# MCH_CON.net
KiCad netlist of a schematic drawn in Altium Designer
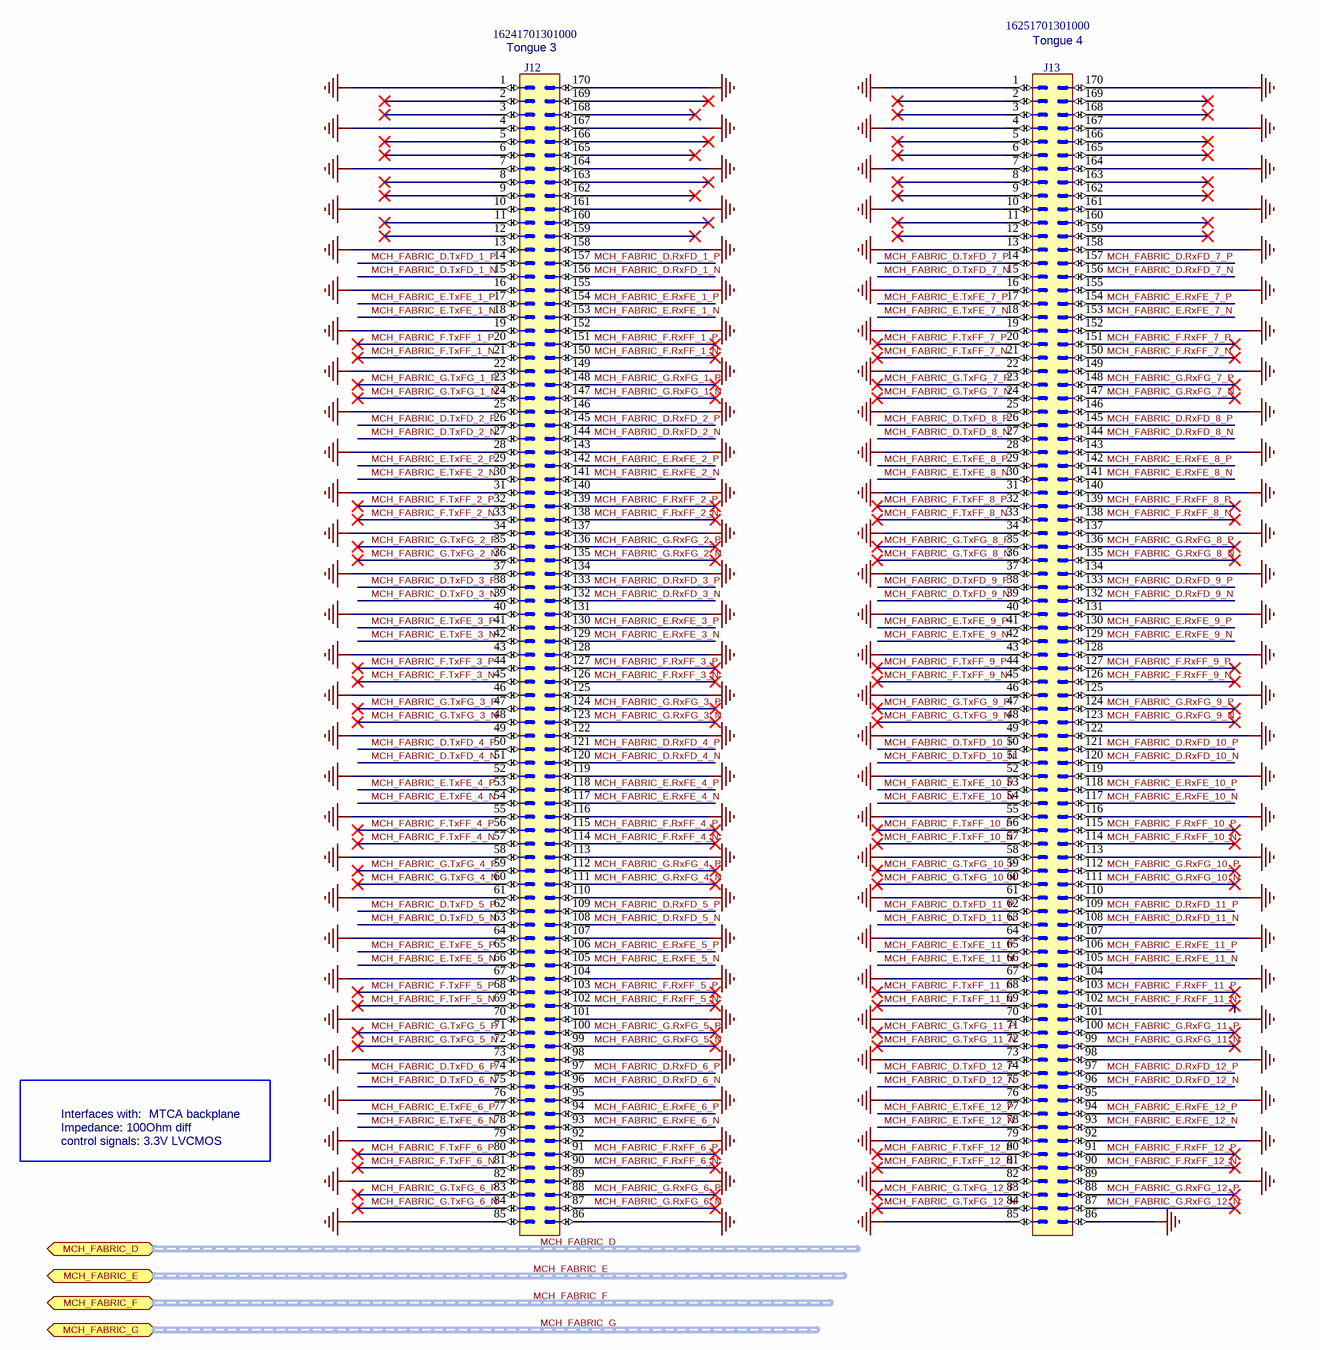
[diagram p0: MCH_CON.SchDoc]

(export (version "E")
  (design (tool "Eeschema 10.0.6"))
  (components
    (comp (ref "J12")
      (value "AdvancedMC")
      (footprint "ITB_16241701301000")
      (description "Connector 170 Male")
      (fields
        (field (name "MANUFACTURER PART NUMBER") "16241701301000")
        (field (name "MANUFACTURER") "ITB ADVANCED CONNECTORS")
        (field (name "PART NUMBER") "ITB_16241701301000")
        (field (name "AUTHOR") "CERN DEM MR")
      )
      (libsource (lib "Connectors") (part "Connector 170 Male"))
    )
    (comp (ref "J13")
      (value "AdvancedMC")
      (footprint "ITB_16251701301000")
      (description "Connector 170 Male")
      (fields
        (field (name "MANUFACTURER PART NUMBER") "16251701301000")
        (field (name "MANUFACTURER") "ITB ADVANCED CONNECTORS")
        (field (name "PART NUMBER") "ITB_16251701301000")
        (field (name "AUTHOR") "CERN DEM MR")
      )
      (libsource (lib "Connectors") (part "Connector 170 Male"))
    )
  )
  (nets
    (net (code "5") (name "/MCH_FABRIC_D.RxFD_1_N") (class "Default")
      (node (ref "J12") (pin "156") (pinfunction "156_156") (pintype "bidirectional"))
    )
    (net (code "6") (name "/MCH_FABRIC_D.RxFD_1_P") (class "Default")
      (node (ref "J12") (pin "157") (pinfunction "157_157") (pintype "bidirectional"))
    )
    (net (code "7") (name "/MCH_FABRIC_D.RxFD_2_N") (class "Default")
      (node (ref "J12") (pin "144") (pinfunction "144_144") (pintype "bidirectional"))
    )
    (net (code "8") (name "/MCH_FABRIC_D.RxFD_2_P") (class "Default")
      (node (ref "J12") (pin "145") (pinfunction "145_145") (pintype "bidirectional"))
    )
    (net (code "9") (name "/MCH_FABRIC_D.RxFD_3_N") (class "Default")
      (node (ref "J12") (pin "132") (pinfunction "132_132") (pintype "bidirectional"))
    )
    (net (code "10") (name "/MCH_FABRIC_D.RxFD_3_P") (class "Default")
      (node (ref "J12") (pin "133") (pinfunction "133_133") (pintype "bidirectional"))
    )
    (net (code "11") (name "/MCH_FABRIC_D.RxFD_4_N") (class "Default")
      (node (ref "J12") (pin "120") (pinfunction "120_120") (pintype "bidirectional"))
    )
    (net (code "12") (name "/MCH_FABRIC_D.RxFD_4_P") (class "Default")
      (node (ref "J12") (pin "121") (pinfunction "121_121") (pintype "bidirectional"))
    )
    (net (code "13") (name "/MCH_FABRIC_D.RxFD_5_N") (class "Default")
      (node (ref "J12") (pin "108") (pinfunction "108_108") (pintype "bidirectional"))
    )
    (net (code "14") (name "/MCH_FABRIC_D.RxFD_5_P") (class "Default")
      (node (ref "J12") (pin "109") (pinfunction "109_109") (pintype "bidirectional"))
    )
    (net (code "15") (name "/MCH_FABRIC_D.RxFD_6_N") (class "Default")
      (node (ref "J12") (pin "96") (pinfunction "96_96") (pintype "bidirectional"))
    )
    (net (code "16") (name "/MCH_FABRIC_D.RxFD_6_P") (class "Default")
      (node (ref "J12") (pin "97") (pinfunction "97_97") (pintype "bidirectional"))
    )
    (net (code "17") (name "/MCH_FABRIC_D.RxFD_7_N") (class "Default")
      (node (ref "J13") (pin "156") (pinfunction "156_156") (pintype "bidirectional"))
    )
    (net (code "18") (name "/MCH_FABRIC_D.RxFD_7_P") (class "Default")
      (node (ref "J13") (pin "157") (pinfunction "157_157") (pintype "bidirectional"))
    )
    (net (code "19") (name "/MCH_FABRIC_D.RxFD_8_N") (class "Default")
      (node (ref "J13") (pin "144") (pinfunction "144_144") (pintype "bidirectional"))
    )
    (net (code "20") (name "/MCH_FABRIC_D.RxFD_8_P") (class "Default")
      (node (ref "J13") (pin "145") (pinfunction "145_145") (pintype "bidirectional"))
    )
    (net (code "21") (name "/MCH_FABRIC_D.RxFD_9_N") (class "Default")
      (node (ref "J13") (pin "132") (pinfunction "132_132") (pintype "bidirectional"))
    )
    (net (code "22") (name "/MCH_FABRIC_D.RxFD_9_P") (class "Default")
      (node (ref "J13") (pin "133") (pinfunction "133_133") (pintype "bidirectional"))
    )
    (net (code "23") (name "/MCH_FABRIC_D.RxFD_10_N") (class "Default")
      (node (ref "J13") (pin "120") (pinfunction "120_120") (pintype "bidirectional"))
    )
    (net (code "24") (name "/MCH_FABRIC_D.RxFD_10_P") (class "Default")
      (node (ref "J13") (pin "121") (pinfunction "121_121") (pintype "bidirectional"))
    )
    (net (code "25") (name "/MCH_FABRIC_D.RxFD_11_N") (class "Default")
      (node (ref "J13") (pin "108") (pinfunction "108_108") (pintype "bidirectional"))
    )
    (net (code "26") (name "/MCH_FABRIC_D.RxFD_11_P") (class "Default")
      (node (ref "J13") (pin "109") (pinfunction "109_109") (pintype "bidirectional"))
    )
    (net (code "27") (name "/MCH_FABRIC_D.RxFD_12_N") (class "Default")
      (node (ref "J13") (pin "96") (pinfunction "96_96") (pintype "bidirectional"))
    )
    (net (code "28") (name "/MCH_FABRIC_D.RxFD_12_P") (class "Default")
      (node (ref "J13") (pin "97") (pinfunction "97_97") (pintype "bidirectional"))
    )
    (net (code "29") (name "/MCH_FABRIC_D.TxFD_1_N") (class "Default")
      (node (ref "J12") (pin "15") (pinfunction "29_15") (pintype "bidirectional"))
    )
    (net (code "30") (name "/MCH_FABRIC_D.TxFD_1_P") (class "Default")
      (node (ref "J12") (pin "14") (pinfunction "27_14") (pintype "bidirectional"))
    )
    (net (code "31") (name "/MCH_FABRIC_D.TxFD_2_N") (class "Default")
      (node (ref "J12") (pin "27") (pinfunction "53_27") (pintype "bidirectional"))
    )
    (net (code "32") (name "/MCH_FABRIC_D.TxFD_2_P") (class "Default")
      (node (ref "J12") (pin "26") (pinfunction "51_26") (pintype "bidirectional"))
    )
    (net (code "33") (name "/MCH_FABRIC_D.TxFD_3_N") (class "Default")
      (node (ref "J12") (pin "39") (pinfunction "77_39") (pintype "bidirectional"))
    )
    (net (code "34") (name "/MCH_FABRIC_D.TxFD_3_P") (class "Default")
      (node (ref "J12") (pin "38") (pinfunction "75_38") (pintype "bidirectional"))
    )
    (net (code "35") (name "/MCH_FABRIC_D.TxFD_4_N") (class "Default")
      (node (ref "J12") (pin "51") (pinfunction "101_51") (pintype "bidirectional"))
    )
    (net (code "36") (name "/MCH_FABRIC_D.TxFD_4_P") (class "Default")
      (node (ref "J12") (pin "50") (pinfunction "99_50") (pintype "bidirectional"))
    )
    (net (code "37") (name "/MCH_FABRIC_D.TxFD_5_N") (class "Default")
      (node (ref "J12") (pin "63") (pinfunction "75_63") (pintype "bidirectional"))
    )
    (net (code "38") (name "/MCH_FABRIC_D.TxFD_5_P") (class "Default")
      (node (ref "J12") (pin "62") (pinfunction "73_62") (pintype "bidirectional"))
    )
    (net (code "39") (name "/MCH_FABRIC_D.TxFD_6_N") (class "Default")
      (node (ref "J12") (pin "75") (pinfunction "99_75") (pintype "bidirectional"))
    )
    (net (code "40") (name "/MCH_FABRIC_D.TxFD_6_P") (class "Default")
      (node (ref "J12") (pin "74") (pinfunction "97_74") (pintype "bidirectional"))
    )
    (net (code "41") (name "/MCH_FABRIC_D.TxFD_7_N") (class "Default")
      (node (ref "J13") (pin "15") (pinfunction "29_15") (pintype "bidirectional"))
    )
    (net (code "42") (name "/MCH_FABRIC_D.TxFD_7_P") (class "Default")
      (node (ref "J13") (pin "14") (pinfunction "27_14") (pintype "bidirectional"))
    )
    (net (code "43") (name "/MCH_FABRIC_D.TxFD_8_N") (class "Default")
      (node (ref "J13") (pin "27") (pinfunction "53_27") (pintype "bidirectional"))
    )
    (net (code "44") (name "/MCH_FABRIC_D.TxFD_8_P") (class "Default")
      (node (ref "J13") (pin "26") (pinfunction "51_26") (pintype "bidirectional"))
    )
    (net (code "45") (name "/MCH_FABRIC_D.TxFD_9_N") (class "Default")
      (node (ref "J13") (pin "39") (pinfunction "77_39") (pintype "bidirectional"))
    )
    (net (code "46") (name "/MCH_FABRIC_D.TxFD_9_P") (class "Default")
      (node (ref "J13") (pin "38") (pinfunction "75_38") (pintype "bidirectional"))
    )
    (net (code "47") (name "/MCH_FABRIC_D.TxFD_10_N") (class "Default")
      (node (ref "J13") (pin "51") (pinfunction "101_51") (pintype "bidirectional"))
    )
    (net (code "48") (name "/MCH_FABRIC_D.TxFD_10_P") (class "Default")
      (node (ref "J13") (pin "50") (pinfunction "99_50") (pintype "bidirectional"))
    )
    (net (code "49") (name "/MCH_FABRIC_D.TxFD_11_N") (class "Default")
      (node (ref "J13") (pin "63") (pinfunction "75_63") (pintype "bidirectional"))
    )
    (net (code "50") (name "/MCH_FABRIC_D.TxFD_11_P") (class "Default")
      (node (ref "J13") (pin "62") (pinfunction "73_62") (pintype "bidirectional"))
    )
    (net (code "51") (name "/MCH_FABRIC_D.TxFD_12_N") (class "Default")
      (node (ref "J13") (pin "75") (pinfunction "99_75") (pintype "bidirectional"))
    )
    (net (code "52") (name "/MCH_FABRIC_D.TxFD_12_P") (class "Default")
      (node (ref "J13") (pin "74") (pinfunction "97_74") (pintype "bidirectional"))
    )
    (net (code "53") (name "/MCH_FABRIC_E.RxFE_1_N") (class "Default")
      (node (ref "J12") (pin "153") (pinfunction "153_153") (pintype "bidirectional"))
    )
    (net (code "54") (name "/MCH_FABRIC_E.RxFE_1_P") (class "Default")
      (node (ref "J12") (pin "154") (pinfunction "154_154") (pintype "bidirectional"))
    )
    (net (code "55") (name "/MCH_FABRIC_E.RxFE_2_N") (class "Default")
      (node (ref "J12") (pin "141") (pinfunction "141_141") (pintype "bidirectional"))
    )
    (net (code "56") (name "/MCH_FABRIC_E.RxFE_2_P") (class "Default")
      (node (ref "J12") (pin "142") (pinfunction "142_142") (pintype "bidirectional"))
    )
    (net (code "57") (name "/MCH_FABRIC_E.RxFE_3_N") (class "Default")
      (node (ref "J12") (pin "129") (pinfunction "129_129") (pintype "bidirectional"))
    )
    (net (code "58") (name "/MCH_FABRIC_E.RxFE_3_P") (class "Default")
      (node (ref "J12") (pin "130") (pinfunction "130_130") (pintype "bidirectional"))
    )
    (net (code "59") (name "/MCH_FABRIC_E.RxFE_4_N") (class "Default")
      (node (ref "J12") (pin "117") (pinfunction "117_117") (pintype "bidirectional"))
    )
    (net (code "60") (name "/MCH_FABRIC_E.RxFE_4_P") (class "Default")
      (node (ref "J12") (pin "118") (pinfunction "118_118") (pintype "bidirectional"))
    )
    (net (code "61") (name "/MCH_FABRIC_E.RxFE_5_N") (class "Default")
      (node (ref "J12") (pin "105") (pinfunction "105_105") (pintype "bidirectional"))
    )
    (net (code "62") (name "/MCH_FABRIC_E.RxFE_5_P") (class "Default")
      (node (ref "J12") (pin "106") (pinfunction "106_106") (pintype "bidirectional"))
    )
    (net (code "63") (name "/MCH_FABRIC_E.RxFE_6_N") (class "Default")
      (node (ref "J12") (pin "93") (pinfunction "93_93") (pintype "bidirectional"))
    )
    (net (code "64") (name "/MCH_FABRIC_E.RxFE_6_P") (class "Default")
      (node (ref "J12") (pin "94") (pinfunction "94_94") (pintype "bidirectional"))
    )
    (net (code "65") (name "/MCH_FABRIC_E.RxFE_7_N") (class "Default")
      (node (ref "J13") (pin "153") (pinfunction "153_153") (pintype "bidirectional"))
    )
    (net (code "66") (name "/MCH_FABRIC_E.RxFE_7_P") (class "Default")
      (node (ref "J13") (pin "154") (pinfunction "154_154") (pintype "bidirectional"))
    )
    (net (code "67") (name "/MCH_FABRIC_E.RxFE_8_N") (class "Default")
      (node (ref "J13") (pin "141") (pinfunction "141_141") (pintype "bidirectional"))
    )
    (net (code "68") (name "/MCH_FABRIC_E.RxFE_8_P") (class "Default")
      (node (ref "J13") (pin "142") (pinfunction "142_142") (pintype "bidirectional"))
    )
    (net (code "69") (name "/MCH_FABRIC_E.RxFE_9_N") (class "Default")
      (node (ref "J13") (pin "129") (pinfunction "129_129") (pintype "bidirectional"))
    )
    (net (code "70") (name "/MCH_FABRIC_E.RxFE_9_P") (class "Default")
      (node (ref "J13") (pin "130") (pinfunction "130_130") (pintype "bidirectional"))
    )
    (net (code "71") (name "/MCH_FABRIC_E.RxFE_10_N") (class "Default")
      (node (ref "J13") (pin "117") (pinfunction "117_117") (pintype "bidirectional"))
    )
    (net (code "72") (name "/MCH_FABRIC_E.RxFE_10_P") (class "Default")
      (node (ref "J13") (pin "118") (pinfunction "118_118") (pintype "bidirectional"))
    )
    (net (code "73") (name "/MCH_FABRIC_E.RxFE_11_N") (class "Default")
      (node (ref "J13") (pin "105") (pinfunction "105_105") (pintype "bidirectional"))
    )
    (net (code "74") (name "/MCH_FABRIC_E.RxFE_11_P") (class "Default")
      (node (ref "J13") (pin "106") (pinfunction "106_106") (pintype "bidirectional"))
    )
    (net (code "75") (name "/MCH_FABRIC_E.RxFE_12_N") (class "Default")
      (node (ref "J13") (pin "93") (pinfunction "93_93") (pintype "bidirectional"))
    )
    (net (code "76") (name "/MCH_FABRIC_E.RxFE_12_P") (class "Default")
      (node (ref "J13") (pin "94") (pinfunction "94_94") (pintype "bidirectional"))
    )
    (net (code "77") (name "/MCH_FABRIC_E.TxFE_1_N") (class "Default")
      (node (ref "J12") (pin "18") (pinfunction "35_18") (pintype "bidirectional"))
    )
    (net (code "78") (name "/MCH_FABRIC_E.TxFE_1_P") (class "Default")
      (node (ref "J12") (pin "17") (pinfunction "33_17") (pintype "bidirectional"))
    )
    (net (code "79") (name "/MCH_FABRIC_E.TxFE_2_N") (class "Default")
      (node (ref "J12") (pin "30") (pinfunction "59_30") (pintype "bidirectional"))
    )
    (net (code "80") (name "/MCH_FABRIC_E.TxFE_2_P") (class "Default")
      (node (ref "J12") (pin "29") (pinfunction "57_29") (pintype "bidirectional"))
    )
    (net (code "81") (name "/MCH_FABRIC_E.TxFE_3_N") (class "Default")
      (node (ref "J12") (pin "42") (pinfunction "83_42") (pintype "bidirectional"))
    )
    (net (code "82") (name "/MCH_FABRIC_E.TxFE_3_P") (class "Default")
      (node (ref "J12") (pin "41") (pinfunction "81_41") (pintype "bidirectional"))
    )
    (net (code "83") (name "/MCH_FABRIC_E.TxFE_4_N") (class "Default")
      (node (ref "J12") (pin "54") (pinfunction "107_54") (pintype "bidirectional"))
    )
    (net (code "84") (name "/MCH_FABRIC_E.TxFE_4_P") (class "Default")
      (node (ref "J12") (pin "53") (pinfunction "105_53") (pintype "bidirectional"))
    )
    (net (code "85") (name "/MCH_FABRIC_E.TxFE_5_N") (class "Default")
      (node (ref "J12") (pin "66") (pinfunction "81_66") (pintype "bidirectional"))
    )
    (net (code "86") (name "/MCH_FABRIC_E.TxFE_5_P") (class "Default")
      (node (ref "J12") (pin "65") (pinfunction "79_65") (pintype "bidirectional"))
    )
    (net (code "87") (name "/MCH_FABRIC_E.TxFE_6_N") (class "Default")
      (node (ref "J12") (pin "78") (pinfunction "105_78") (pintype "bidirectional"))
    )
    (net (code "88") (name "/MCH_FABRIC_E.TxFE_6_P") (class "Default")
      (node (ref "J12") (pin "77") (pinfunction "103_77") (pintype "bidirectional"))
    )
    (net (code "89") (name "/MCH_FABRIC_E.TxFE_7_N") (class "Default")
      (node (ref "J13") (pin "18") (pinfunction "35_18") (pintype "bidirectional"))
    )
    (net (code "90") (name "/MCH_FABRIC_E.TxFE_7_P") (class "Default")
      (node (ref "J13") (pin "17") (pinfunction "33_17") (pintype "bidirectional"))
    )
    (net (code "91") (name "/MCH_FABRIC_E.TxFE_8_N") (class "Default")
      (node (ref "J13") (pin "30") (pinfunction "59_30") (pintype "bidirectional"))
    )
    (net (code "92") (name "/MCH_FABRIC_E.TxFE_8_P") (class "Default")
      (node (ref "J13") (pin "29") (pinfunction "57_29") (pintype "bidirectional"))
    )
    (net (code "93") (name "/MCH_FABRIC_E.TxFE_9_N") (class "Default")
      (node (ref "J13") (pin "42") (pinfunction "83_42") (pintype "bidirectional"))
    )
    (net (code "94") (name "/MCH_FABRIC_E.TxFE_9_P") (class "Default")
      (node (ref "J13") (pin "41") (pinfunction "81_41") (pintype "bidirectional"))
    )
    (net (code "95") (name "/MCH_FABRIC_E.TxFE_10_N") (class "Default")
      (node (ref "J13") (pin "54") (pinfunction "107_54") (pintype "bidirectional"))
    )
    (net (code "96") (name "/MCH_FABRIC_E.TxFE_10_P") (class "Default")
      (node (ref "J13") (pin "53") (pinfunction "105_53") (pintype "bidirectional"))
    )
    (net (code "97") (name "/MCH_FABRIC_E.TxFE_11_N") (class "Default")
      (node (ref "J13") (pin "66") (pinfunction "81_66") (pintype "bidirectional"))
    )
    (net (code "98") (name "/MCH_FABRIC_E.TxFE_11_P") (class "Default")
      (node (ref "J13") (pin "65") (pinfunction "79_65") (pintype "bidirectional"))
    )
    (net (code "99") (name "/MCH_FABRIC_E.TxFE_12_N") (class "Default")
      (node (ref "J13") (pin "78") (pinfunction "105_78") (pintype "bidirectional"))
    )
    (net (code "100") (name "/MCH_FABRIC_E.TxFE_12_P") (class "Default")
      (node (ref "J13") (pin "77") (pinfunction "103_77") (pintype "bidirectional"))
    )
    (net (code "101") (name "/MCH_FABRIC_F.RxFF_1_N") (class "Default")
      (node (ref "J12") (pin "150") (pinfunction "150_150") (pintype "bidirectional+no_connect"))
    )
    (net (code "102") (name "/MCH_FABRIC_F.RxFF_1_P") (class "Default")
      (node (ref "J12") (pin "151") (pinfunction "151_151") (pintype "bidirectional+no_connect"))
    )
    (net (code "103") (name "/MCH_FABRIC_F.RxFF_2_N") (class "Default")
      (node (ref "J12") (pin "138") (pinfunction "138_138") (pintype "bidirectional+no_connect"))
    )
    (net (code "104") (name "/MCH_FABRIC_F.RxFF_2_P") (class "Default")
      (node (ref "J12") (pin "139") (pinfunction "139_139") (pintype "bidirectional+no_connect"))
    )
    (net (code "105") (name "/MCH_FABRIC_F.RxFF_3_N") (class "Default")
      (node (ref "J12") (pin "126") (pinfunction "126_126") (pintype "bidirectional+no_connect"))
    )
    (net (code "106") (name "/MCH_FABRIC_F.RxFF_3_P") (class "Default")
      (node (ref "J12") (pin "127") (pinfunction "127_127") (pintype "bidirectional+no_connect"))
    )
    (net (code "107") (name "/MCH_FABRIC_F.RxFF_4_N") (class "Default")
      (node (ref "J12") (pin "114") (pinfunction "114_114") (pintype "bidirectional+no_connect"))
    )
    (net (code "108") (name "/MCH_FABRIC_F.RxFF_4_P") (class "Default")
      (node (ref "J12") (pin "115") (pinfunction "115_115") (pintype "bidirectional+no_connect"))
    )
    (net (code "109") (name "/MCH_FABRIC_F.RxFF_5_N") (class "Default")
      (node (ref "J12") (pin "102") (pinfunction "102_102") (pintype "bidirectional+no_connect"))
    )
    (net (code "110") (name "/MCH_FABRIC_F.RxFF_5_P") (class "Default")
      (node (ref "J12") (pin "103") (pinfunction "103_103") (pintype "bidirectional+no_connect"))
    )
    (net (code "111") (name "/MCH_FABRIC_F.RxFF_6_N") (class "Default")
      (node (ref "J12") (pin "90") (pinfunction "90_90") (pintype "bidirectional+no_connect"))
    )
    (net (code "112") (name "/MCH_FABRIC_F.RxFF_6_P") (class "Default")
      (node (ref "J12") (pin "91") (pinfunction "91_91") (pintype "bidirectional+no_connect"))
    )
    (net (code "113") (name "/MCH_FABRIC_F.RxFF_7_N") (class "Default")
      (node (ref "J13") (pin "150") (pinfunction "150_150") (pintype "bidirectional+no_connect"))
    )
    (net (code "114") (name "/MCH_FABRIC_F.RxFF_7_P") (class "Default")
      (node (ref "J13") (pin "151") (pinfunction "151_151") (pintype "bidirectional+no_connect"))
    )
    (net (code "115") (name "/MCH_FABRIC_F.RxFF_8_N") (class "Default")
      (node (ref "J13") (pin "138") (pinfunction "138_138") (pintype "bidirectional+no_connect"))
    )
    (net (code "116") (name "/MCH_FABRIC_F.RxFF_8_P") (class "Default")
      (node (ref "J13") (pin "139") (pinfunction "139_139") (pintype "bidirectional+no_connect"))
    )
    (net (code "117") (name "/MCH_FABRIC_F.RxFF_9_N") (class "Default")
      (node (ref "J13") (pin "126") (pinfunction "126_126") (pintype "bidirectional+no_connect"))
    )
    (net (code "118") (name "/MCH_FABRIC_F.RxFF_9_P") (class "Default")
      (node (ref "J13") (pin "127") (pinfunction "127_127") (pintype "bidirectional+no_connect"))
    )
    (net (code "119") (name "/MCH_FABRIC_F.RxFF_10_N") (class "Default")
      (node (ref "J13") (pin "114") (pinfunction "114_114") (pintype "bidirectional+no_connect"))
    )
    (net (code "120") (name "/MCH_FABRIC_F.RxFF_10_P") (class "Default")
      (node (ref "J13") (pin "115") (pinfunction "115_115") (pintype "bidirectional+no_connect"))
    )
    (net (code "121") (name "/MCH_FABRIC_F.RxFF_11_N") (class "Default")
      (node (ref "J13") (pin "102") (pinfunction "102_102") (pintype "bidirectional+no_connect"))
    )
    (net (code "122") (name "/MCH_FABRIC_F.RxFF_11_P") (class "Default")
      (node (ref "J13") (pin "103") (pinfunction "103_103") (pintype "bidirectional+no_connect"))
    )
    (net (code "123") (name "/MCH_FABRIC_F.RxFF_12_N") (class "Default")
      (node (ref "J13") (pin "90") (pinfunction "90_90") (pintype "bidirectional+no_connect"))
    )
    (net (code "124") (name "/MCH_FABRIC_F.RxFF_12_P") (class "Default")
      (node (ref "J13") (pin "91") (pinfunction "91_91") (pintype "bidirectional+no_connect"))
    )
    (net (code "125") (name "/MCH_FABRIC_F.TxFF_1_N") (class "Default")
      (node (ref "J12") (pin "21") (pinfunction "41_21") (pintype "bidirectional+no_connect"))
    )
    (net (code "126") (name "/MCH_FABRIC_F.TxFF_1_P") (class "Default")
      (node (ref "J12") (pin "20") (pinfunction "39_20") (pintype "bidirectional+no_connect"))
    )
    (net (code "127") (name "/MCH_FABRIC_F.TxFF_2_N") (class "Default")
      (node (ref "J12") (pin "33") (pinfunction "65_33") (pintype "bidirectional+no_connect"))
    )
    (net (code "128") (name "/MCH_FABRIC_F.TxFF_2_P") (class "Default")
      (node (ref "J12") (pin "32") (pinfunction "63_32") (pintype "bidirectional+no_connect"))
    )
    (net (code "129") (name "/MCH_FABRIC_F.TxFF_3_N") (class "Default")
      (node (ref "J12") (pin "45") (pinfunction "89_45") (pintype "bidirectional+no_connect"))
    )
    (net (code "130") (name "/MCH_FABRIC_F.TxFF_3_P") (class "Default")
      (node (ref "J12") (pin "44") (pinfunction "87_44") (pintype "bidirectional+no_connect"))
    )
    (net (code "131") (name "/MCH_FABRIC_F.TxFF_4_N") (class "Default")
      (node (ref "J12") (pin "57") (pinfunction "113_57") (pintype "bidirectional+no_connect"))
    )
    (net (code "132") (name "/MCH_FABRIC_F.TxFF_4_P") (class "Default")
      (node (ref "J12") (pin "56") (pinfunction "111_56") (pintype "bidirectional+no_connect"))
    )
    (net (code "133") (name "/MCH_FABRIC_F.TxFF_5_N") (class "Default")
      (node (ref "J12") (pin "69") (pinfunction "87_69") (pintype "bidirectional+no_connect"))
    )
    (net (code "134") (name "/MCH_FABRIC_F.TxFF_5_P") (class "Default")
      (node (ref "J12") (pin "68") (pinfunction "85_68") (pintype "bidirectional+no_connect"))
    )
    (net (code "135") (name "/MCH_FABRIC_F.TxFF_6_N") (class "Default")
      (node (ref "J12") (pin "81") (pinfunction "111_81") (pintype "bidirectional+no_connect"))
    )
    (net (code "136") (name "/MCH_FABRIC_F.TxFF_6_P") (class "Default")
      (node (ref "J12") (pin "80") (pinfunction "109_80") (pintype "bidirectional+no_connect"))
    )
    (net (code "137") (name "/MCH_FABRIC_F.TxFF_7_N") (class "Default")
      (node (ref "J13") (pin "21") (pinfunction "41_21") (pintype "bidirectional+no_connect"))
    )
    (net (code "138") (name "/MCH_FABRIC_F.TxFF_7_P") (class "Default")
      (node (ref "J13") (pin "20") (pinfunction "39_20") (pintype "bidirectional+no_connect"))
    )
    (net (code "139") (name "/MCH_FABRIC_F.TxFF_8_N") (class "Default")
      (node (ref "J13") (pin "33") (pinfunction "65_33") (pintype "bidirectional+no_connect"))
    )
    (net (code "140") (name "/MCH_FABRIC_F.TxFF_8_P") (class "Default")
      (node (ref "J13") (pin "32") (pinfunction "63_32") (pintype "bidirectional+no_connect"))
    )
    (net (code "141") (name "/MCH_FABRIC_F.TxFF_9_N") (class "Default")
      (node (ref "J13") (pin "45") (pinfunction "89_45") (pintype "bidirectional+no_connect"))
    )
    (net (code "142") (name "/MCH_FABRIC_F.TxFF_9_P") (class "Default")
      (node (ref "J13") (pin "44") (pinfunction "87_44") (pintype "bidirectional+no_connect"))
    )
    (net (code "143") (name "/MCH_FABRIC_F.TxFF_10_N") (class "Default")
      (node (ref "J13") (pin "57") (pinfunction "113_57") (pintype "bidirectional+no_connect"))
    )
    (net (code "144") (name "/MCH_FABRIC_F.TxFF_10_P") (class "Default")
      (node (ref "J13") (pin "56") (pinfunction "111_56") (pintype "bidirectional+no_connect"))
    )
    (net (code "145") (name "/MCH_FABRIC_F.TxFF_11_N") (class "Default")
      (node (ref "J13") (pin "69") (pinfunction "87_69") (pintype "bidirectional+no_connect"))
    )
    (net (code "146") (name "/MCH_FABRIC_F.TxFF_11_P") (class "Default")
      (node (ref "J13") (pin "68") (pinfunction "85_68") (pintype "bidirectional+no_connect"))
    )
    (net (code "147") (name "/MCH_FABRIC_F.TxFF_12_N") (class "Default")
      (node (ref "J13") (pin "81") (pinfunction "111_81") (pintype "bidirectional+no_connect"))
    )
    (net (code "148") (name "/MCH_FABRIC_F.TxFF_12_P") (class "Default")
      (node (ref "J13") (pin "80") (pinfunction "109_80") (pintype "bidirectional+no_connect"))
    )
    (net (code "149") (name "/MCH_FABRIC_G.RxFG_1_N") (class "Default")
      (node (ref "J12") (pin "147") (pinfunction "147_147") (pintype "bidirectional+no_connect"))
    )
    (net (code "150") (name "/MCH_FABRIC_G.RxFG_1_P") (class "Default")
      (node (ref "J12") (pin "148") (pinfunction "148_148") (pintype "bidirectional+no_connect"))
    )
    (net (code "151") (name "/MCH_FABRIC_G.RxFG_2_N") (class "Default")
      (node (ref "J12") (pin "135") (pinfunction "135_135") (pintype "bidirectional+no_connect"))
    )
    (net (code "152") (name "/MCH_FABRIC_G.RxFG_2_P") (class "Default")
      (node (ref "J12") (pin "136") (pinfunction "136_136") (pintype "bidirectional+no_connect"))
    )
    (net (code "153") (name "/MCH_FABRIC_G.RxFG_3_N") (class "Default")
      (node (ref "J12") (pin "123") (pinfunction "123_123") (pintype "bidirectional+no_connect"))
    )
    (net (code "154") (name "/MCH_FABRIC_G.RxFG_3_P") (class "Default")
      (node (ref "J12") (pin "124") (pinfunction "124_124") (pintype "bidirectional+no_connect"))
    )
    (net (code "155") (name "/MCH_FABRIC_G.RxFG_4_N") (class "Default")
      (node (ref "J12") (pin "111") (pinfunction "111_111") (pintype "bidirectional+no_connect"))
    )
    (net (code "156") (name "/MCH_FABRIC_G.RxFG_4_P") (class "Default")
      (node (ref "J12") (pin "112") (pinfunction "112_112") (pintype "bidirectional+no_connect"))
    )
    (net (code "157") (name "/MCH_FABRIC_G.RxFG_5_N") (class "Default")
      (node (ref "J12") (pin "99") (pinfunction "99_99") (pintype "bidirectional+no_connect"))
    )
    (net (code "158") (name "/MCH_FABRIC_G.RxFG_5_P") (class "Default")
      (node (ref "J12") (pin "100") (pinfunction "100_100") (pintype "bidirectional+no_connect"))
    )
    (net (code "159") (name "/MCH_FABRIC_G.RxFG_6_N") (class "Default")
      (node (ref "J12") (pin "87") (pinfunction "87_87") (pintype "bidirectional+no_connect"))
    )
    (net (code "160") (name "/MCH_FABRIC_G.RxFG_6_P") (class "Default")
      (node (ref "J12") (pin "88") (pinfunction "88_88") (pintype "bidirectional+no_connect"))
    )
    (net (code "161") (name "/MCH_FABRIC_G.RxFG_7_N") (class "Default")
      (node (ref "J13") (pin "147") (pinfunction "147_147") (pintype "bidirectional+no_connect"))
    )
    (net (code "162") (name "/MCH_FABRIC_G.RxFG_7_P") (class "Default")
      (node (ref "J13") (pin "148") (pinfunction "148_148") (pintype "bidirectional+no_connect"))
    )
    (net (code "163") (name "/MCH_FABRIC_G.RxFG_8_N") (class "Default")
      (node (ref "J13") (pin "135") (pinfunction "135_135") (pintype "bidirectional+no_connect"))
    )
    (net (code "164") (name "/MCH_FABRIC_G.RxFG_8_P") (class "Default")
      (node (ref "J13") (pin "136") (pinfunction "136_136") (pintype "bidirectional+no_connect"))
    )
    (net (code "165") (name "/MCH_FABRIC_G.RxFG_9_N") (class "Default")
      (node (ref "J13") (pin "123") (pinfunction "123_123") (pintype "bidirectional+no_connect"))
    )
    (net (code "166") (name "/MCH_FABRIC_G.RxFG_9_P") (class "Default")
      (node (ref "J13") (pin "124") (pinfunction "124_124") (pintype "bidirectional+no_connect"))
    )
    (net (code "167") (name "/MCH_FABRIC_G.RxFG_10_N") (class "Default")
      (node (ref "J13") (pin "111") (pinfunction "111_111") (pintype "bidirectional+no_connect"))
    )
    (net (code "168") (name "/MCH_FABRIC_G.RxFG_10_P") (class "Default")
      (node (ref "J13") (pin "112") (pinfunction "112_112") (pintype "bidirectional+no_connect"))
    )
    (net (code "169") (name "/MCH_FABRIC_G.RxFG_11_N") (class "Default")
      (node (ref "J13") (pin "99") (pinfunction "99_99") (pintype "bidirectional+no_connect"))
    )
    (net (code "170") (name "/MCH_FABRIC_G.RxFG_11_P") (class "Default")
      (node (ref "J13") (pin "100") (pinfunction "100_100") (pintype "bidirectional+no_connect"))
    )
    (net (code "171") (name "/MCH_FABRIC_G.RxFG_12_N") (class "Default")
      (node (ref "J13") (pin "87") (pinfunction "87_87") (pintype "bidirectional+no_connect"))
    )
    (net (code "172") (name "/MCH_FABRIC_G.RxFG_12_P") (class "Default")
      (node (ref "J13") (pin "88") (pinfunction "88_88") (pintype "bidirectional+no_connect"))
    )
    (net (code "173") (name "/MCH_FABRIC_G.TxFG_1_N") (class "Default")
      (node (ref "J12") (pin "24") (pinfunction "47_24") (pintype "bidirectional+no_connect"))
    )
    (net (code "174") (name "/MCH_FABRIC_G.TxFG_1_P") (class "Default")
      (node (ref "J12") (pin "23") (pinfunction "45_23") (pintype "bidirectional+no_connect"))
    )
    (net (code "175") (name "/MCH_FABRIC_G.TxFG_2_N") (class "Default")
      (node (ref "J12") (pin "36") (pinfunction "71_36") (pintype "bidirectional+no_connect"))
    )
    (net (code "176") (name "/MCH_FABRIC_G.TxFG_2_P") (class "Default")
      (node (ref "J12") (pin "35") (pinfunction "69_35") (pintype "bidirectional+no_connect"))
    )
    (net (code "177") (name "/MCH_FABRIC_G.TxFG_3_N") (class "Default")
      (node (ref "J12") (pin "48") (pinfunction "95_48") (pintype "bidirectional+no_connect"))
    )
    (net (code "178") (name "/MCH_FABRIC_G.TxFG_3_P") (class "Default")
      (node (ref "J12") (pin "47") (pinfunction "93_47") (pintype "bidirectional+no_connect"))
    )
    (net (code "179") (name "/MCH_FABRIC_G.TxFG_4_N") (class "Default")
      (node (ref "J12") (pin "60") (pinfunction "119_60") (pintype "bidirectional+no_connect"))
    )
    (net (code "180") (name "/MCH_FABRIC_G.TxFG_4_P") (class "Default")
      (node (ref "J12") (pin "59") (pinfunction "117_59") (pintype "bidirectional+no_connect"))
    )
    (net (code "181") (name "/MCH_FABRIC_G.TxFG_5_N") (class "Default")
      (node (ref "J12") (pin "72") (pinfunction "93_72") (pintype "bidirectional+no_connect"))
    )
    (net (code "182") (name "/MCH_FABRIC_G.TxFG_5_P") (class "Default")
      (node (ref "J12") (pin "71") (pinfunction "91_71") (pintype "bidirectional+no_connect"))
    )
    (net (code "183") (name "/MCH_FABRIC_G.TxFG_6_N") (class "Default")
      (node (ref "J12") (pin "84") (pinfunction "117_84") (pintype "bidirectional+no_connect"))
    )
    (net (code "184") (name "/MCH_FABRIC_G.TxFG_6_P") (class "Default")
      (node (ref "J12") (pin "83") (pinfunction "115_83") (pintype "bidirectional+no_connect"))
    )
    (net (code "185") (name "/MCH_FABRIC_G.TxFG_7_N") (class "Default")
      (node (ref "J13") (pin "24") (pinfunction "47_24") (pintype "bidirectional+no_connect"))
    )
    (net (code "186") (name "/MCH_FABRIC_G.TxFG_7_P") (class "Default")
      (node (ref "J13") (pin "23") (pinfunction "45_23") (pintype "bidirectional+no_connect"))
    )
    (net (code "187") (name "/MCH_FABRIC_G.TxFG_8_N") (class "Default")
      (node (ref "J13") (pin "36") (pinfunction "71_36") (pintype "bidirectional+no_connect"))
    )
    (net (code "188") (name "/MCH_FABRIC_G.TxFG_8_P") (class "Default")
      (node (ref "J13") (pin "35") (pinfunction "69_35") (pintype "bidirectional+no_connect"))
    )
    (net (code "189") (name "/MCH_FABRIC_G.TxFG_9_N") (class "Default")
      (node (ref "J13") (pin "48") (pinfunction "95_48") (pintype "bidirectional+no_connect"))
    )
    (net (code "190") (name "/MCH_FABRIC_G.TxFG_9_P") (class "Default")
      (node (ref "J13") (pin "47") (pinfunction "93_47") (pintype "bidirectional+no_connect"))
    )
    (net (code "191") (name "/MCH_FABRIC_G.TxFG_10_N") (class "Default")
      (node (ref "J13") (pin "60") (pinfunction "119_60") (pintype "bidirectional+no_connect"))
    )
    (net (code "192") (name "/MCH_FABRIC_G.TxFG_10_P") (class "Default")
      (node (ref "J13") (pin "59") (pinfunction "117_59") (pintype "bidirectional+no_connect"))
    )
    (net (code "193") (name "/MCH_FABRIC_G.TxFG_11_N") (class "Default")
      (node (ref "J13") (pin "72") (pinfunction "93_72") (pintype "bidirectional+no_connect"))
    )
    (net (code "194") (name "/MCH_FABRIC_G.TxFG_11_P") (class "Default")
      (node (ref "J13") (pin "71") (pinfunction "91_71") (pintype "bidirectional+no_connect"))
    )
    (net (code "195") (name "/MCH_FABRIC_G.TxFG_12_N") (class "Default")
      (node (ref "J13") (pin "84") (pinfunction "117_84") (pintype "bidirectional+no_connect"))
    )
    (net (code "196") (name "/MCH_FABRIC_G.TxFG_12_P") (class "Default")
      (node (ref "J13") (pin "83") (pinfunction "115_83") (pintype "bidirectional+no_connect"))
    )
    (net (code "201") (name "GND") (class "Default")
      (node (ref "J12") (pin "1") (pinfunction "1_1") (pintype "bidirectional"))
      (node (ref "J12") (pin "10") (pinfunction "19_10") (pintype "bidirectional"))
      (node (ref "J12") (pin "101") (pinfunction "101_101") (pintype "bidirectional"))
      (node (ref "J12") (pin "104") (pinfunction "104_104") (pintype "bidirectional"))
      (node (ref "J12") (pin "107") (pinfunction "107_107") (pintype "bidirectional"))
      (node (ref "J12") (pin "110") (pinfunction "110_110") (pintype "bidirectional"))
      (node (ref "J12") (pin "113") (pinfunction "113_113") (pintype "bidirectional"))
      (node (ref "J12") (pin "116") (pinfunction "116_116") (pintype "bidirectional"))
      (node (ref "J12") (pin "119") (pinfunction "119_119") (pintype "bidirectional"))
      (node (ref "J12") (pin "122") (pinfunction "122_122") (pintype "bidirectional"))
      (node (ref "J12") (pin "125") (pinfunction "125_125") (pintype "bidirectional"))
      (node (ref "J12") (pin "128") (pinfunction "128_128") (pintype "bidirectional"))
      (node (ref "J12") (pin "13") (pinfunction "25_13") (pintype "bidirectional"))
      (node (ref "J12") (pin "131") (pinfunction "131_131") (pintype "bidirectional"))
      (node (ref "J12") (pin "134") (pinfunction "134_134") (pintype "bidirectional"))
      (node (ref "J12") (pin "137") (pinfunction "137_137") (pintype "bidirectional"))
      (node (ref "J12") (pin "140") (pinfunction "140_140") (pintype "bidirectional"))
      (node (ref "J12") (pin "143") (pinfunction "143_143") (pintype "bidirectional"))
      (node (ref "J12") (pin "146") (pinfunction "146_146") (pintype "bidirectional"))
      (node (ref "J12") (pin "149") (pinfunction "149_149") (pintype "bidirectional"))
      (node (ref "J12") (pin "152") (pinfunction "152_152") (pintype "bidirectional"))
      (node (ref "J12") (pin "155") (pinfunction "155_155") (pintype "bidirectional"))
      (node (ref "J12") (pin "158") (pinfunction "158_158") (pintype "bidirectional"))
      (node (ref "J12") (pin "16") (pinfunction "31_16") (pintype "bidirectional"))
      (node (ref "J12") (pin "161") (pinfunction "161_161") (pintype "bidirectional"))
      (node (ref "J12") (pin "164") (pinfunction "164_164") (pintype "bidirectional"))
      (node (ref "J12") (pin "167") (pinfunction "167_167") (pintype "bidirectional"))
      (node (ref "J12") (pin "170") (pinfunction "170_170") (pintype "bidirectional"))
      (node (ref "J12") (pin "19") (pinfunction "37_19") (pintype "bidirectional"))
      (node (ref "J12") (pin "22") (pinfunction "43_22") (pintype "bidirectional"))
      (node (ref "J12") (pin "25") (pinfunction "49_25") (pintype "bidirectional"))
      (node (ref "J12") (pin "28") (pinfunction "55_28") (pintype "bidirectional"))
      (node (ref "J12") (pin "31") (pinfunction "61_31") (pintype "bidirectional"))
      (node (ref "J12") (pin "34") (pinfunction "67_34") (pintype "bidirectional"))
      (node (ref "J12") (pin "37") (pinfunction "73_37") (pintype "bidirectional"))
      (node (ref "J12") (pin "4") (pinfunction "7_4") (pintype "bidirectional"))
      (node (ref "J12") (pin "40") (pinfunction "79_40") (pintype "bidirectional"))
      (node (ref "J12") (pin "43") (pinfunction "85_43") (pintype "bidirectional"))
      (node (ref "J12") (pin "46") (pinfunction "91_46") (pintype "bidirectional"))
      (node (ref "J12") (pin "49") (pinfunction "97_49") (pintype "bidirectional"))
      (node (ref "J12") (pin "52") (pinfunction "103_52") (pintype "bidirectional"))
      (node (ref "J12") (pin "55") (pinfunction "109_55") (pintype "bidirectional"))
      (node (ref "J12") (pin "58") (pinfunction "115_58") (pintype "bidirectional"))
      (node (ref "J12") (pin "61") (pinfunction "71_61") (pintype "bidirectional"))
      (node (ref "J12") (pin "64") (pinfunction "77_64") (pintype "bidirectional"))
      (node (ref "J12") (pin "67") (pinfunction "83_67") (pintype "bidirectional"))
      (node (ref "J12") (pin "7") (pinfunction "13_7") (pintype "bidirectional"))
      (node (ref "J12") (pin "70") (pinfunction "89_70") (pintype "bidirectional"))
      (node (ref "J12") (pin "73") (pinfunction "95_73") (pintype "bidirectional"))
      (node (ref "J12") (pin "76") (pinfunction "101_76") (pintype "bidirectional"))
      (node (ref "J12") (pin "79") (pinfunction "107_79") (pintype "bidirectional"))
      (node (ref "J12") (pin "82") (pinfunction "113_82") (pintype "bidirectional"))
      (node (ref "J12") (pin "85") (pinfunction "119_85") (pintype "bidirectional"))
      (node (ref "J12") (pin "86") (pinfunction "86_86") (pintype "bidirectional"))
      (node (ref "J12") (pin "89") (pinfunction "89_89") (pintype "bidirectional"))
      (node (ref "J12") (pin "92") (pinfunction "92_92") (pintype "bidirectional"))
      (node (ref "J12") (pin "95") (pinfunction "95_95") (pintype "bidirectional"))
      (node (ref "J12") (pin "98") (pinfunction "98_98") (pintype "bidirectional"))
      (node (ref "J13") (pin "1") (pinfunction "1_1") (pintype "bidirectional"))
      (node (ref "J13") (pin "10") (pinfunction "19_10") (pintype "bidirectional"))
      (node (ref "J13") (pin "101") (pinfunction "101_101") (pintype "bidirectional"))
      (node (ref "J13") (pin "104") (pinfunction "104_104") (pintype "bidirectional"))
      (node (ref "J13") (pin "107") (pinfunction "107_107") (pintype "bidirectional"))
      (node (ref "J13") (pin "110") (pinfunction "110_110") (pintype "bidirectional"))
      (node (ref "J13") (pin "113") (pinfunction "113_113") (pintype "bidirectional"))
      (node (ref "J13") (pin "116") (pinfunction "116_116") (pintype "bidirectional"))
      (node (ref "J13") (pin "119") (pinfunction "119_119") (pintype "bidirectional"))
      (node (ref "J13") (pin "122") (pinfunction "122_122") (pintype "bidirectional"))
      (node (ref "J13") (pin "125") (pinfunction "125_125") (pintype "bidirectional"))
      (node (ref "J13") (pin "128") (pinfunction "128_128") (pintype "bidirectional"))
      (node (ref "J13") (pin "13") (pinfunction "25_13") (pintype "bidirectional"))
      (node (ref "J13") (pin "131") (pinfunction "131_131") (pintype "bidirectional"))
      (node (ref "J13") (pin "134") (pinfunction "134_134") (pintype "bidirectional"))
      (node (ref "J13") (pin "137") (pinfunction "137_137") (pintype "bidirectional"))
      (node (ref "J13") (pin "140") (pinfunction "140_140") (pintype "bidirectional"))
      (node (ref "J13") (pin "143") (pinfunction "143_143") (pintype "bidirectional"))
      (node (ref "J13") (pin "146") (pinfunction "146_146") (pintype "bidirectional"))
      (node (ref "J13") (pin "149") (pinfunction "149_149") (pintype "bidirectional"))
      (node (ref "J13") (pin "152") (pinfunction "152_152") (pintype "bidirectional"))
      (node (ref "J13") (pin "155") (pinfunction "155_155") (pintype "bidirectional"))
      (node (ref "J13") (pin "158") (pinfunction "158_158") (pintype "bidirectional"))
      (node (ref "J13") (pin "16") (pinfunction "31_16") (pintype "bidirectional"))
      (node (ref "J13") (pin "161") (pinfunction "161_161") (pintype "bidirectional"))
      (node (ref "J13") (pin "164") (pinfunction "164_164") (pintype "bidirectional"))
      (node (ref "J13") (pin "167") (pinfunction "167_167") (pintype "bidirectional"))
      (node (ref "J13") (pin "170") (pinfunction "170_170") (pintype "bidirectional"))
      (node (ref "J13") (pin "19") (pinfunction "37_19") (pintype "bidirectional"))
      (node (ref "J13") (pin "22") (pinfunction "43_22") (pintype "bidirectional"))
      (node (ref "J13") (pin "25") (pinfunction "49_25") (pintype "bidirectional"))
      (node (ref "J13") (pin "28") (pinfunction "55_28") (pintype "bidirectional"))
      (node (ref "J13") (pin "31") (pinfunction "61_31") (pintype "bidirectional"))
      (node (ref "J13") (pin "34") (pinfunction "67_34") (pintype "bidirectional"))
      (node (ref "J13") (pin "37") (pinfunction "73_37") (pintype "bidirectional"))
      (node (ref "J13") (pin "4") (pinfunction "7_4") (pintype "bidirectional"))
      (node (ref "J13") (pin "40") (pinfunction "79_40") (pintype "bidirectional"))
      (node (ref "J13") (pin "43") (pinfunction "85_43") (pintype "bidirectional"))
      (node (ref "J13") (pin "46") (pinfunction "91_46") (pintype "bidirectional"))
      (node (ref "J13") (pin "49") (pinfunction "97_49") (pintype "bidirectional"))
      (node (ref "J13") (pin "52") (pinfunction "103_52") (pintype "bidirectional"))
      (node (ref "J13") (pin "55") (pinfunction "109_55") (pintype "bidirectional"))
      (node (ref "J13") (pin "58") (pinfunction "115_58") (pintype "bidirectional"))
      (node (ref "J13") (pin "61") (pinfunction "71_61") (pintype "bidirectional"))
      (node (ref "J13") (pin "64") (pinfunction "77_64") (pintype "bidirectional"))
      (node (ref "J13") (pin "67") (pinfunction "83_67") (pintype "bidirectional"))
      (node (ref "J13") (pin "7") (pinfunction "13_7") (pintype "bidirectional"))
      (node (ref "J13") (pin "70") (pinfunction "89_70") (pintype "bidirectional"))
      (node (ref "J13") (pin "73") (pinfunction "95_73") (pintype "bidirectional"))
      (node (ref "J13") (pin "76") (pinfunction "101_76") (pintype "bidirectional"))
      (node (ref "J13") (pin "79") (pinfunction "107_79") (pintype "bidirectional"))
      (node (ref "J13") (pin "82") (pinfunction "113_82") (pintype "bidirectional"))
      (node (ref "J13") (pin "85") (pinfunction "119_85") (pintype "bidirectional"))
      (node (ref "J13") (pin "86") (pinfunction "86_86") (pintype "bidirectional"))
      (node (ref "J13") (pin "89") (pinfunction "89_89") (pintype "bidirectional"))
      (node (ref "J13") (pin "92") (pinfunction "92_92") (pintype "bidirectional"))
      (node (ref "J13") (pin "95") (pinfunction "95_95") (pintype "bidirectional"))
      (node (ref "J13") (pin "98") (pinfunction "98_98") (pintype "bidirectional"))
    )
    (net (code "202") (name "unconnected-(J12-3-Pad2)") (class "Default")
      (node (ref "J12") (pin "2") (pinfunction "3_2") (pintype "bidirectional+no_connect"))
    )
    (net (code "203") (name "unconnected-(J12-5-Pad3)") (class "Default")
      (node (ref "J12") (pin "3") (pinfunction "5_3") (pintype "bidirectional+no_connect"))
    )
    (net (code "204") (name "unconnected-(J12-9-Pad5)") (class "Default")
      (node (ref "J12") (pin "5") (pinfunction "9_5") (pintype "bidirectional+no_connect"))
    )
    (net (code "205") (name "unconnected-(J12-11-Pad6)") (class "Default")
      (node (ref "J12") (pin "6") (pinfunction "11_6") (pintype "bidirectional+no_connect"))
    )
    (net (code "206") (name "unconnected-(J12-15-Pad8)") (class "Default")
      (node (ref "J12") (pin "8") (pinfunction "15_8") (pintype "bidirectional+no_connect"))
    )
    (net (code "207") (name "unconnected-(J12-17-Pad9)") (class "Default")
      (node (ref "J12") (pin "9") (pinfunction "17_9") (pintype "bidirectional+no_connect"))
    )
    (net (code "208") (name "unconnected-(J12-21-Pad11)") (class "Default")
      (node (ref "J12") (pin "11") (pinfunction "21_11") (pintype "bidirectional+no_connect"))
    )
    (net (code "209") (name "unconnected-(J12-23-Pad12)") (class "Default")
      (node (ref "J12") (pin "12") (pinfunction "23_12") (pintype "bidirectional+no_connect"))
    )
    (net (code "210") (name "unconnected-(J12-Pad159)") (class "Default")
      (node (ref "J12") (pin "159") (pinfunction "159_159") (pintype "bidirectional+no_connect"))
    )
    (net (code "211") (name "unconnected-(J12-Pad160)") (class "Default")
      (node (ref "J12") (pin "160") (pinfunction "160_160") (pintype "bidirectional+no_connect"))
    )
    (net (code "212") (name "unconnected-(J12-Pad162)") (class "Default")
      (node (ref "J12") (pin "162") (pinfunction "162_162") (pintype "bidirectional+no_connect"))
    )
    (net (code "213") (name "unconnected-(J12-Pad163)") (class "Default")
      (node (ref "J12") (pin "163") (pinfunction "163_163") (pintype "bidirectional+no_connect"))
    )
    (net (code "214") (name "unconnected-(J12-Pad165)") (class "Default")
      (node (ref "J12") (pin "165") (pinfunction "165_165") (pintype "bidirectional+no_connect"))
    )
    (net (code "215") (name "unconnected-(J12-Pad166)") (class "Default")
      (node (ref "J12") (pin "166") (pinfunction "166_166") (pintype "bidirectional+no_connect"))
    )
    (net (code "216") (name "unconnected-(J12-Pad168)") (class "Default")
      (node (ref "J12") (pin "168") (pinfunction "168_168") (pintype "bidirectional+no_connect"))
    )
    (net (code "217") (name "unconnected-(J12-Pad169)") (class "Default")
      (node (ref "J12") (pin "169") (pinfunction "169_169") (pintype "bidirectional+no_connect"))
    )
    (net (code "218") (name "unconnected-(J13-3-Pad2)") (class "Default")
      (node (ref "J13") (pin "2") (pinfunction "3_2") (pintype "bidirectional+no_connect"))
    )
    (net (code "219") (name "unconnected-(J13-5-Pad3)") (class "Default")
      (node (ref "J13") (pin "3") (pinfunction "5_3") (pintype "bidirectional+no_connect"))
    )
    (net (code "220") (name "unconnected-(J13-9-Pad5)") (class "Default")
      (node (ref "J13") (pin "5") (pinfunction "9_5") (pintype "bidirectional+no_connect"))
    )
    (net (code "221") (name "unconnected-(J13-11-Pad6)") (class "Default")
      (node (ref "J13") (pin "6") (pinfunction "11_6") (pintype "bidirectional+no_connect"))
    )
    (net (code "222") (name "unconnected-(J13-15-Pad8)") (class "Default")
      (node (ref "J13") (pin "8") (pinfunction "15_8") (pintype "bidirectional+no_connect"))
    )
    (net (code "223") (name "unconnected-(J13-17-Pad9)") (class "Default")
      (node (ref "J13") (pin "9") (pinfunction "17_9") (pintype "bidirectional+no_connect"))
    )
    (net (code "224") (name "unconnected-(J13-21-Pad11)") (class "Default")
      (node (ref "J13") (pin "11") (pinfunction "21_11") (pintype "bidirectional+no_connect"))
    )
    (net (code "225") (name "unconnected-(J13-23-Pad12)") (class "Default")
      (node (ref "J13") (pin "12") (pinfunction "23_12") (pintype "bidirectional+no_connect"))
    )
    (net (code "226") (name "unconnected-(J13-Pad159)") (class "Default")
      (node (ref "J13") (pin "159") (pinfunction "159_159") (pintype "bidirectional+no_connect"))
    )
    (net (code "227") (name "unconnected-(J13-Pad160)") (class "Default")
      (node (ref "J13") (pin "160") (pinfunction "160_160") (pintype "bidirectional+no_connect"))
    )
    (net (code "228") (name "unconnected-(J13-Pad162)") (class "Default")
      (node (ref "J13") (pin "162") (pinfunction "162_162") (pintype "bidirectional+no_connect"))
    )
    (net (code "229") (name "unconnected-(J13-Pad163)") (class "Default")
      (node (ref "J13") (pin "163") (pinfunction "163_163") (pintype "bidirectional+no_connect"))
    )
    (net (code "230") (name "unconnected-(J13-Pad165)") (class "Default")
      (node (ref "J13") (pin "165") (pinfunction "165_165") (pintype "bidirectional+no_connect"))
    )
    (net (code "231") (name "unconnected-(J13-Pad166)") (class "Default")
      (node (ref "J13") (pin "166") (pinfunction "166_166") (pintype "bidirectional+no_connect"))
    )
    (net (code "232") (name "unconnected-(J13-Pad168)") (class "Default")
      (node (ref "J13") (pin "168") (pinfunction "168_168") (pintype "bidirectional+no_connect"))
    )
    (net (code "233") (name "unconnected-(J13-Pad169)") (class "Default")
      (node (ref "J13") (pin "169") (pinfunction "169_169") (pintype "bidirectional+no_connect"))
    )
  )
)
